# SCH_NFC-Card-Patrick_2024-10-10.net
KiCad netlist of a schematic drawn in EasyEDA
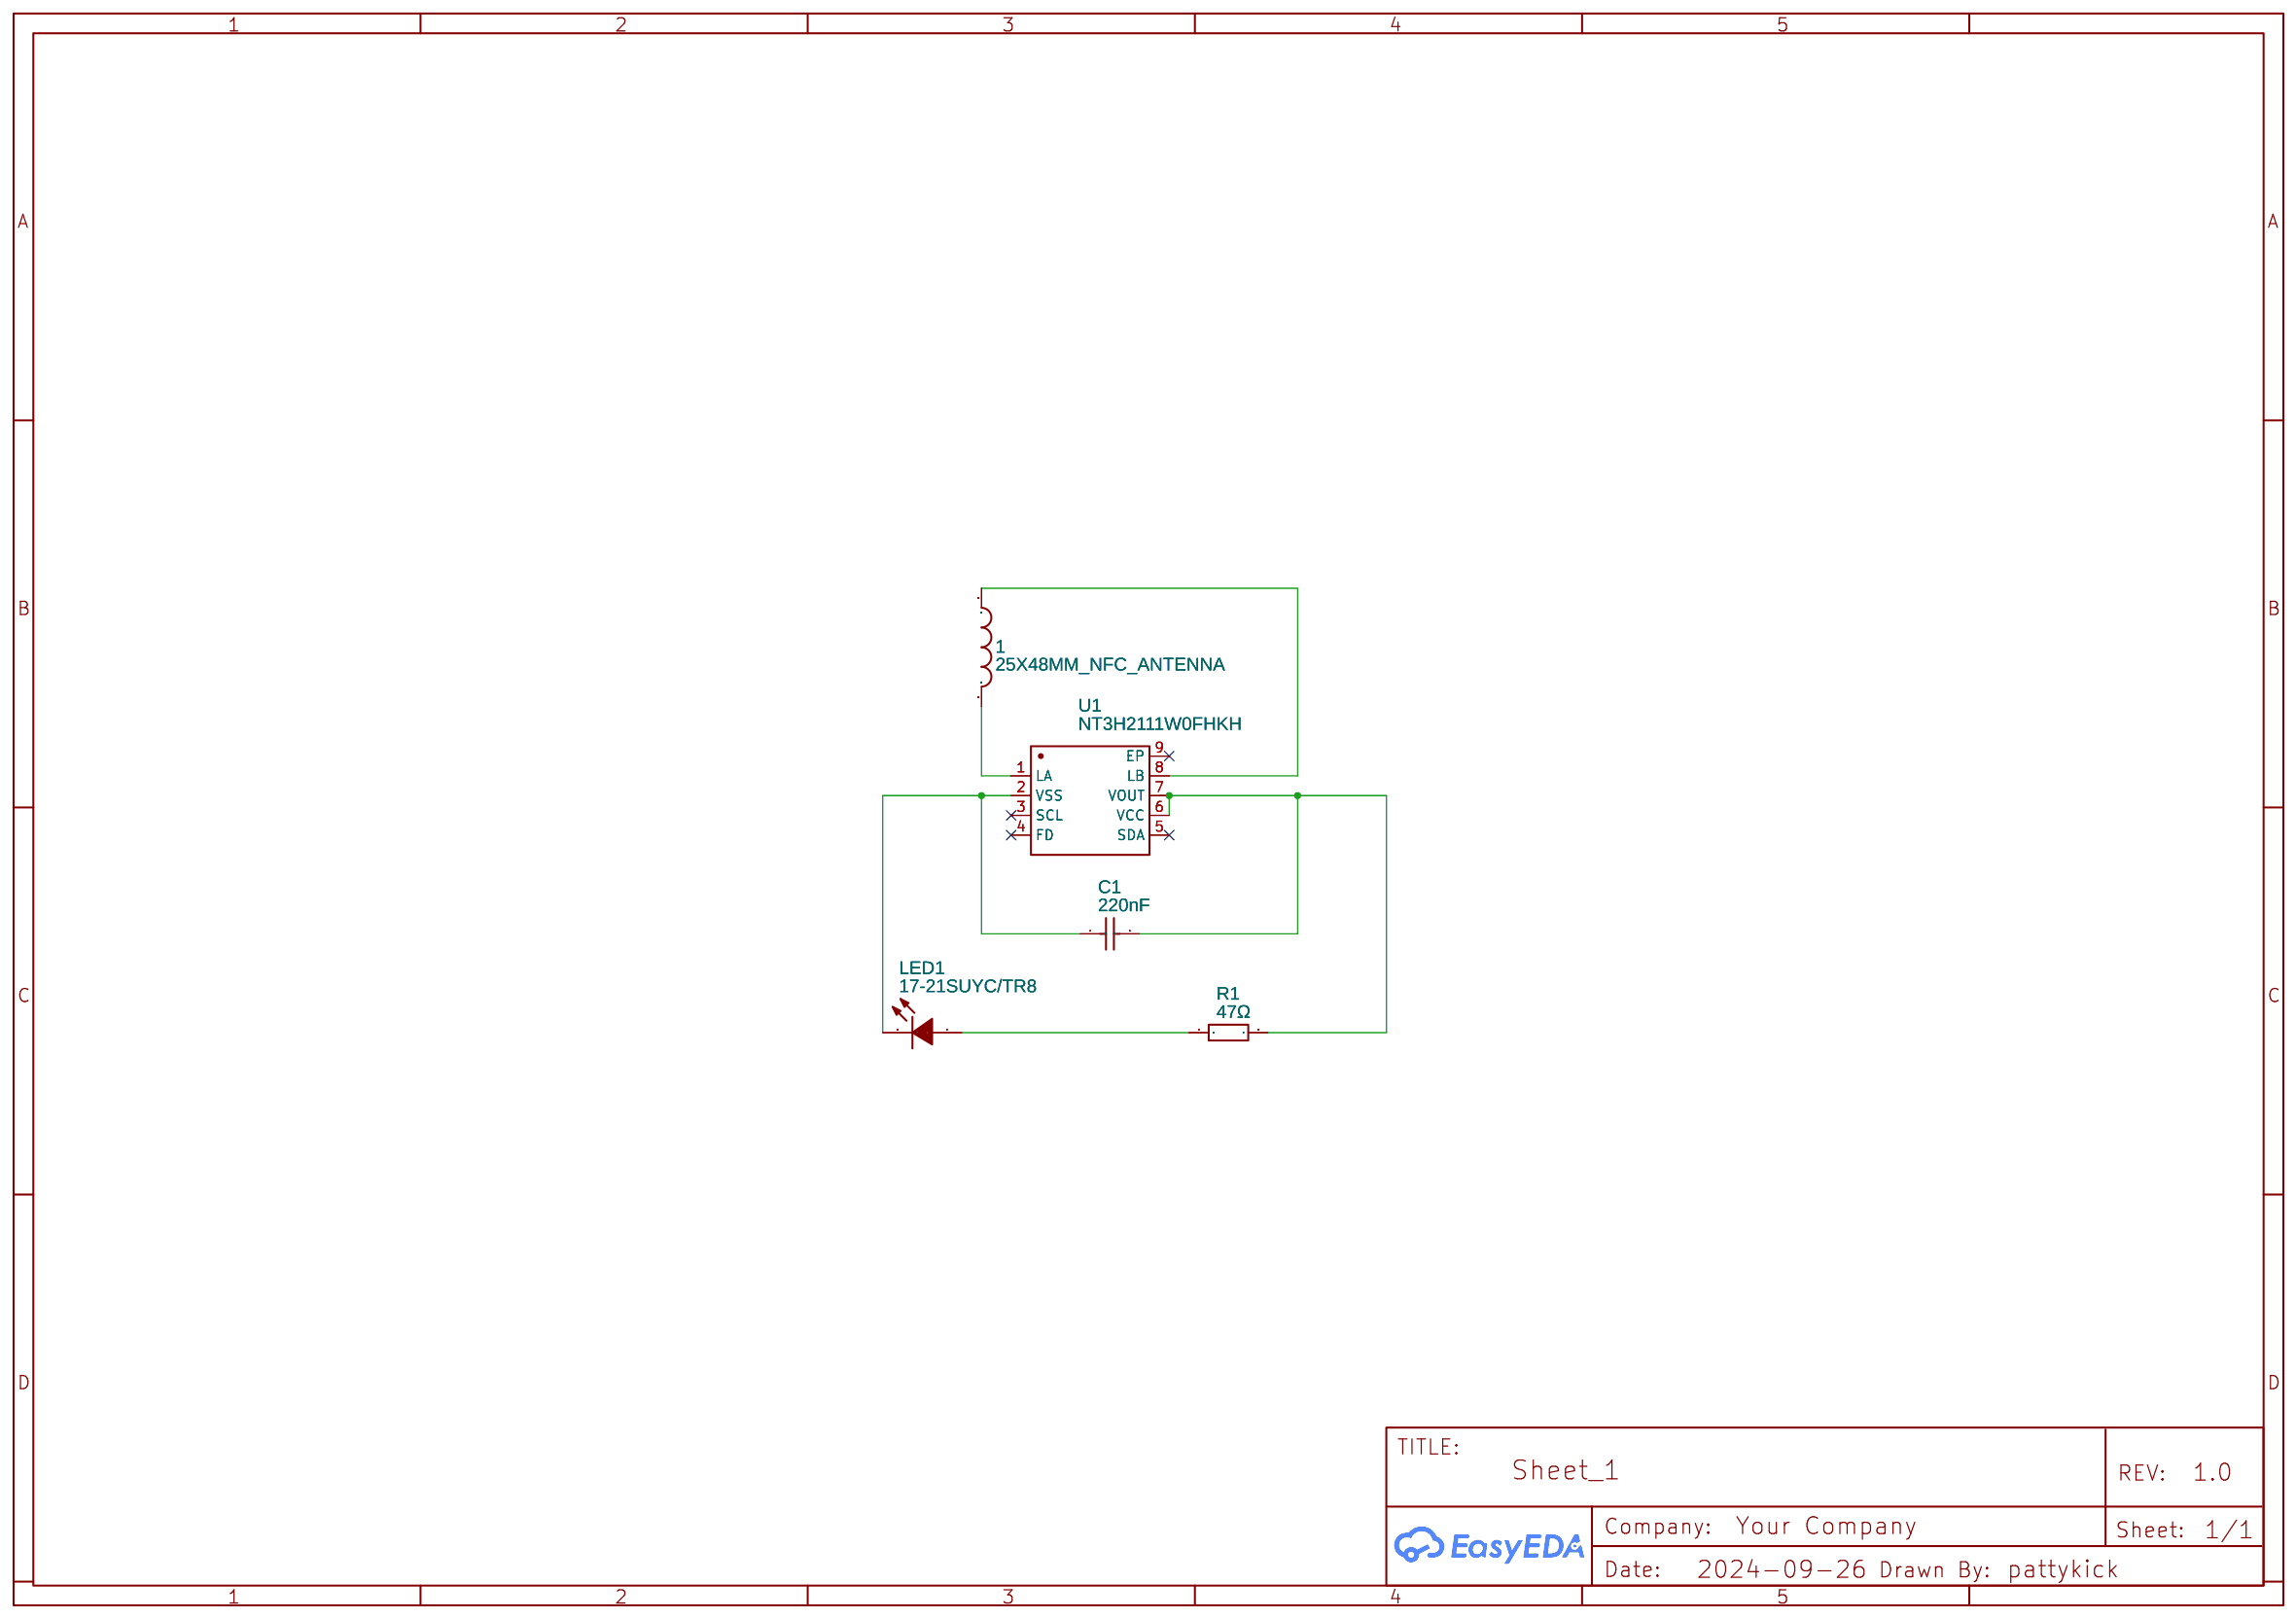
[diagram p0: schematic sheet]

(export (version "E")
  (design (tool "Eeschema 10.0.6"))
  (components
    (comp (ref "1") (value "25X48MM_NFC_ANTENNA") (libsource (lib "") (part "25X48MM_NFC_ANTENNA")))
    (comp (ref "C1")
      (value "220nF")
      (fields
        (field (name "Manufacturer Part") "CL10B224KA8NNNC")
        (field (name "Manufacturer") "SAMSUNG(三星)")
      )
      (libsource (lib "") (part "CL10B224KA8NNNC"))
    )
    (comp (ref "LED1")
      (value "17-21SUYC/TR8")
      (fields (field (name "Manufacturer Part") "KT-0805黄灯") (field (name "Manufacturer") "KENTO"))
      (libsource (lib "") (part "17-21SUYC/TR8"))
    )
    (comp (ref "R1")
      (value "47Ω")
      (fields
        (field (name "Manufacturer Part") "0603WAF470JT5E")
        (field (name "Manufacturer") "UNI-ROYAL(厚声)")
      )
      (libsource (lib "") (part "0603WAF470JT5E"))
    )
    (comp (ref "U1")
      (value "NT3H2111W0FHKH")
      (fields (field (name "Manufacturer") "NXP(恩智浦)"))
      (libsource (lib "") (part "NT3H2111W0FHKH"))
    )
  )
  (nets
    (net (code "1") (name "Net-(LED1-+)") (class "Default")
      (node (ref "LED1") (pin "1") (pinfunction "+_1") (pintype "unspecified"))
      (node (ref "R1") (pin "1") (pinfunction "1_1") (pintype "input"))
    )
    (net (code "2") (name "Net-(LED1--)") (class "Default")
      (node (ref "C1") (pin "1") (pinfunction "1_1") (pintype "input"))
      (node (ref "LED1") (pin "2") (pinfunction "-_2") (pintype "unspecified"))
      (node (ref "U1") (pin "2") (pinfunction "VSS_2") (pintype "unspecified"))
    )
    (net (code "3") (name "Net-(U1-LA)") (class "Default")
      (node (ref "1") (pin "P$2") (pinfunction "P$2_P$2") (pintype "bidirectional"))
      (node (ref "U1") (pin "1") (pinfunction "LA_1") (pintype "unspecified"))
    )
    (net (code "4") (name "Net-(U1-LB)") (class "Default")
      (node (ref "1") (pin "P$1") (pinfunction "P$1_P$1") (pintype "bidirectional"))
      (node (ref "U1") (pin "8") (pinfunction "LB_8") (pintype "unspecified"))
    )
    (net (code "5") (name "Net-(U1-VCC)") (class "Default")
      (node (ref "C1") (pin "2") (pinfunction "2_2") (pintype "input"))
      (node (ref "R1") (pin "2") (pinfunction "2_2") (pintype "input"))
      (node (ref "U1") (pin "6") (pinfunction "VCC_6") (pintype "unspecified"))
      (node (ref "U1") (pin "7") (pinfunction "VOUT_7") (pintype "unspecified"))
    )
    (net (code "6") (name "unconnected-(U1-EP-Pad9)") (class "Default")
      (node (ref "U1") (pin "9") (pinfunction "EP_9") (pintype "unspecified+no_connect"))
    )
    (net (code "7") (name "unconnected-(U1-FD-Pad4)") (class "Default")
      (node (ref "U1") (pin "4") (pinfunction "FD_4") (pintype "unspecified+no_connect"))
    )
    (net (code "8") (name "unconnected-(U1-SCL-Pad3)") (class "Default")
      (node (ref "U1") (pin "3") (pinfunction "SCL_3") (pintype "unspecified+no_connect"))
    )
    (net (code "9") (name "unconnected-(U1-SDA-Pad5)") (class "Default")
      (node (ref "U1") (pin "5") (pinfunction "SDA_5") (pintype "unspecified+no_connect"))
    )
  )
)
